# MB1297_MEMS.net
KiCad netlist of a schematic drawn in Altium Designer
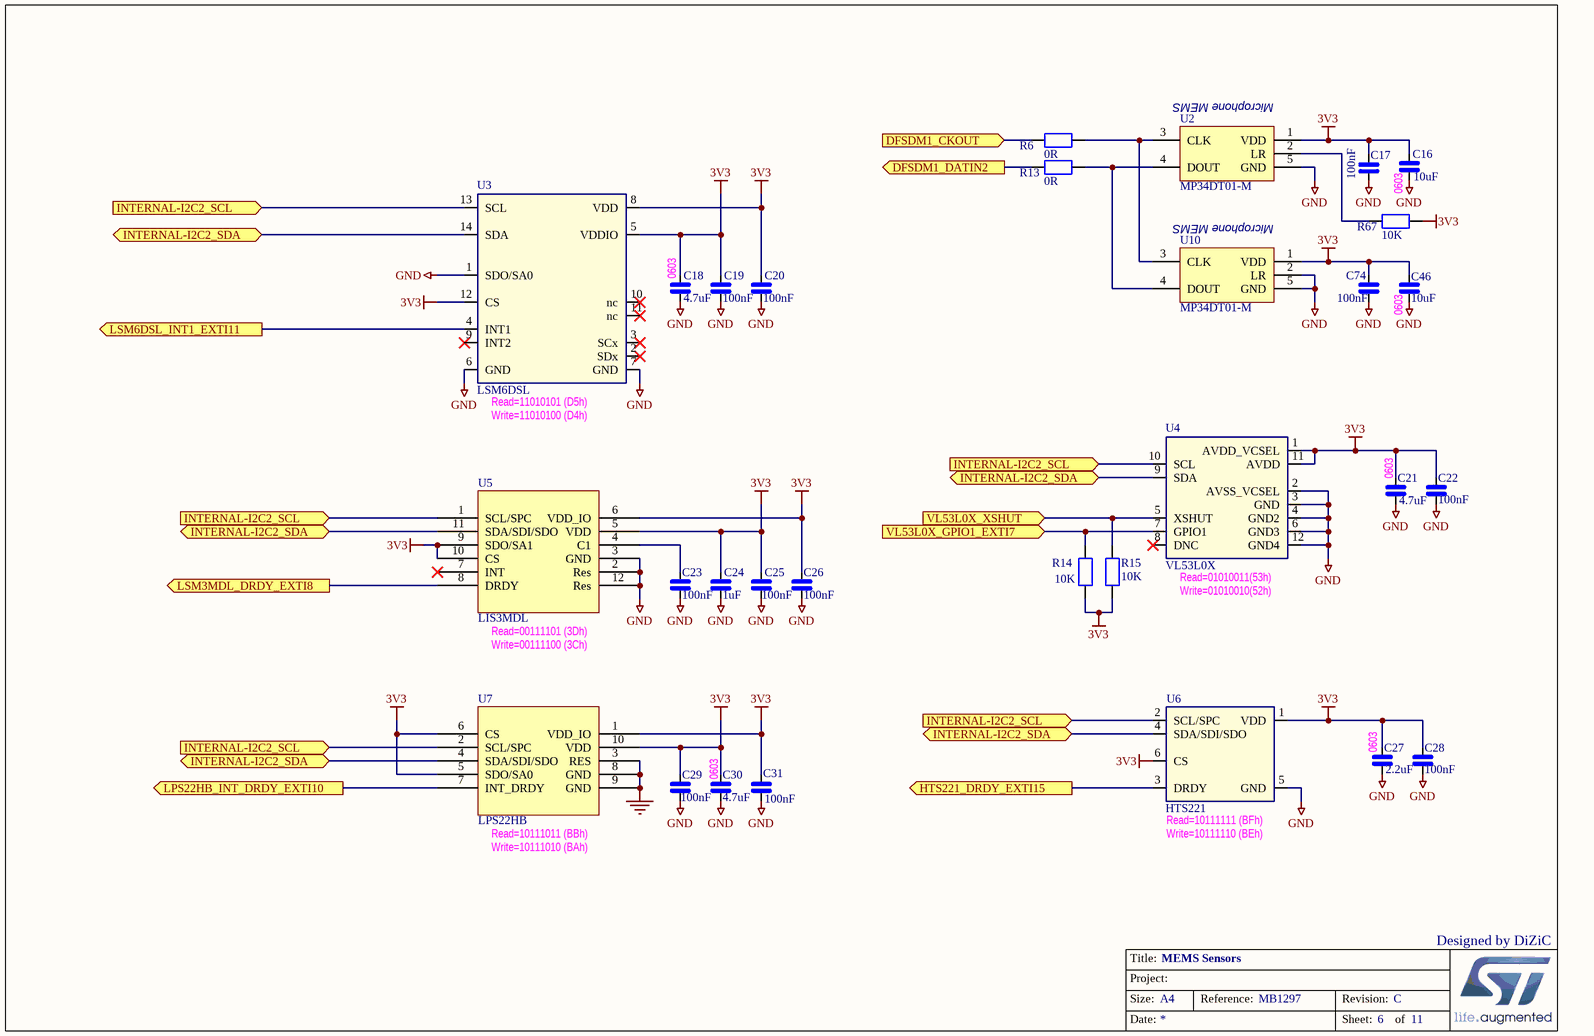
[diagram p0: MB1297_MEMS.SchDoc]

(export (version "E")
  (design (tool "Eeschema 10.0.6"))
  (components
    (comp (ref "C16")
      (value "10uF")
      (footprint "0603_CAP_NPOL")
      (description "Capacitor_not polarized")
      (libsource (lib "ST_Lib3D") (part "CAP_NPOL"))
    )
    (comp (ref "C17")
      (value "100nF")
      (footprint "0402_CAP_NPOL")
      (description "Capacitor_not polarized")
      (libsource (lib "ST_Lib3D") (part "CAP_NPOL"))
    )
    (comp (ref "C18")
      (value "4.7uF")
      (footprint "0603_CAP_NPOL")
      (description "Capacitor_not polarized")
      (libsource (lib "ST_Lib3D") (part "CAP_NPOL"))
    )
    (comp (ref "C19")
      (value "100nF")
      (footprint "0402_CAP_NPOL")
      (description "Capacitor_not polarized")
      (libsource (lib "ST_Lib3D") (part "CAP_NPOL"))
    )
    (comp (ref "C20")
      (value "100nF")
      (footprint "0402_CAP_NPOL")
      (description "Capacitor_not polarized")
      (libsource (lib "ST_Lib3D") (part "CAP_NPOL"))
    )
    (comp (ref "C21")
      (value "4.7uF")
      (footprint "0603_CAP_NPOL")
      (description "Capacitor_not polarized")
      (libsource (lib "ST_Lib3D") (part "CAP_NPOL"))
    )
    (comp (ref "C22")
      (value "100nF")
      (footprint "0402_CAP_NPOL")
      (description "Capacitor_not polarized")
      (libsource (lib "ST_Lib3D") (part "CAP_NPOL"))
    )
    (comp (ref "C23")
      (value "100nF")
      (footprint "0402_CAP_NPOL")
      (description "Capacitor_not polarized")
      (libsource (lib "ST_Lib3D") (part "CAP_NPOL"))
    )
    (comp (ref "C24")
      (value "1uF")
      (footprint "0402_CAP_NPOL")
      (description "Capacitor_not polarized")
      (libsource (lib "ST_Lib3D") (part "CAP_NPOL"))
    )
    (comp (ref "C25")
      (value "100nF")
      (footprint "0402_CAP_NPOL")
      (description "Capacitor_not polarized")
      (libsource (lib "ST_Lib3D") (part "CAP_NPOL"))
    )
    (comp (ref "C26")
      (value "100nF")
      (footprint "0402_CAP_NPOL")
      (description "Capacitor_not polarized")
      (libsource (lib "ST_Lib3D") (part "CAP_NPOL"))
    )
    (comp (ref "C27")
      (value "2.2uF")
      (footprint "0603_CAP_NPOL")
      (description "Capacitor_not polarized")
      (libsource (lib "ST_Lib3D") (part "CAP_NPOL"))
    )
    (comp (ref "C28")
      (value "100nF")
      (footprint "0402_CAP_NPOL")
      (description "Capacitor_not polarized")
      (libsource (lib "ST_Lib3D") (part "CAP_NPOL"))
    )
    (comp (ref "C29")
      (value "100nF")
      (footprint "0402_CAP_NPOL")
      (description "Capacitor_not polarized")
      (libsource (lib "ST_Lib3D") (part "CAP_NPOL"))
    )
    (comp (ref "C30")
      (value "4.7uF")
      (footprint "0603_CAP_NPOL")
      (description "Capacitor_not polarized")
      (libsource (lib "ST_Lib3D") (part "CAP_NPOL"))
    )
    (comp (ref "C31")
      (value "100nF")
      (footprint "0402_CAP_NPOL")
      (description "Capacitor_not polarized")
      (libsource (lib "ST_Lib3D") (part "CAP_NPOL"))
    )
    (comp (ref "C46")
      (value "10uF")
      (footprint "0603_CAP_NPOL")
      (description "Capacitor_not polarized")
      (libsource (lib "MB1297") (part "CAP_NPOL"))
    )
    (comp (ref "C74")
      (value "100nF")
      (footprint "0402_CAP_NPOL")
      (description "Capacitor_not polarized")
      (libsource (lib "MB1297") (part "CAP_NPOL"))
    )
    (comp (ref "R6")
      (value "0R")
      (footprint "0402_RES")
      (description "Resistor")
      (libsource (lib "ST_Lib3D") (part "RES"))
    )
    (comp (ref "R13")
      (value "0R")
      (footprint "0402_RES")
      (description "Resistor")
      (libsource (lib "ST_Lib3D") (part "RES"))
    )
    (comp (ref "R14")
      (value "10K")
      (footprint "0402_RES")
      (description "Resistor")
      (libsource (lib "ST_Lib3D") (part "RES"))
    )
    (comp (ref "R15")
      (value "10K")
      (footprint "0402_RES")
      (description "Resistor")
      (libsource (lib "ST_Lib3D") (part "RES"))
    )
    (comp (ref "R67")
      (value "10K")
      (footprint "0402_RES")
      (description "Resistor")
      (libsource (lib "ST_Lib3D") (part "RES"))
    )
    (comp (ref "U2")
      (value "MP34DT01-M")
      (footprint "HCLGA-4LD 3x4x1")
      (description "MEMS audio microphone")
      (libsource (lib "ST_Lib3D") (part "MP34DT01"))
    )
    (comp (ref "U3")
      (value "LSM6DSL")
      (footprint "LGA14L-2.5X3X0.86p0.5")
      (description "Accelero + Gyro MEMS (6 Axis)")
      (libsource (lib "ST_Lib3D") (part "LSM6DSL"))
    )
    (comp (ref "U4")
      (value "VL53L0X")
      (footprint "LGA12-optical")
      (description "Proximity sensor MEMS")
      (libsource (lib "ST_Lib3D") (part "VL53L0X"))
    )
    (comp (ref "U5")
      (value "LIS3MDL")
      (footprint "VFLGA12-2x2x1")
      (description "IC,Sensor")
      (fields (field (name "PROVIDER") "MMCC"))
      (libsource (lib "Semicon-ST") (part "LIS3MDL"))
    )
    (comp (ref "U6")
      (value "HTS221")
      (footprint "HLGA6L-2x2x0.9")
      (description "Humidity + Temp MEMS")
      (libsource (lib "ST_Lib3D") (part "HTS221"))
    )
    (comp (ref "U7")
      (value "LPS22HB")
      (footprint "HLGA10L-2X2X0.76")
      (description "IC,Sensor")
      (fields (field (name "PROVIDER") "MMCC"))
      (libsource (lib "ST_Lib3D") (part "LPS22HB"))
    )
    (comp (ref "U10")
      (value "MP34DT01-M")
      (footprint "HCLGA-4LD 3x4x1")
      (description "MEMS audio microphone")
      (libsource (lib "MB1297") (part "MP34DT01"))
    )
  )
  (nets
    (net (code "1") (name "/DFSDM1_CKOUT") (class "Default")
      (node (ref "R6") (pin "2") (pinfunction "2_2") (pintype "passive"))
    )
    (net (code "2") (name "/DFSDM1_DATIN2") (class "Default")
      (node (ref "R13") (pin "2") (pinfunction "2_2") (pintype "passive"))
    )
    (net (code "3") (name "/HTS221_DRDY_EXTI15") (class "Default")
      (node (ref "U6") (pin "3") (pinfunction "DRDY_3") (pintype "passive"))
    )
    (net (code "4") (name "/INTERNAL-I2C2_SCL") (class "Default")
      (node (ref "U3") (pin "13") (pinfunction "SCL_13") (pintype "passive"))
      (node (ref "U4") (pin "10") (pinfunction "SCL_10") (pintype "passive"))
      (node (ref "U5") (pin "1") (pinfunction "SCL/SPC_1") (pintype "passive"))
      (node (ref "U6") (pin "2") (pinfunction "SCL/SPC_2") (pintype "passive"))
      (node (ref "U7") (pin "2") (pinfunction "SCL/SPC_2") (pintype "passive"))
    )
    (net (code "5") (name "/INTERNAL-I2C2_SDA") (class "Default")
      (node (ref "U3") (pin "14") (pinfunction "SDA_14") (pintype "passive"))
      (node (ref "U4") (pin "9") (pinfunction "SDA_9") (pintype "passive"))
      (node (ref "U5") (pin "11") (pinfunction "SDA/SDI/SDO_11") (pintype "passive"))
      (node (ref "U6") (pin "4") (pinfunction "SDA/SDI/SDO_4") (pintype "passive"))
      (node (ref "U7") (pin "4") (pinfunction "SDA/SDI/SDO_4") (pintype "passive"))
    )
    (net (code "6") (name "/LPS22HB_INT_DRDY_EXTI10") (class "Default")
      (node (ref "U7") (pin "7") (pinfunction "INT_DRDY_7") (pintype "passive"))
    )
    (net (code "7") (name "/LSM3MDL_DRDY_EXTI8") (class "Default")
      (node (ref "U5") (pin "8") (pinfunction "DRDY_8") (pintype "passive"))
    )
    (net (code "8") (name "/LSM6DSL_INT1_EXTI11") (class "Default")
      (node (ref "U3") (pin "4") (pinfunction "INT1_4") (pintype "passive"))
    )
    (net (code "9") (name "/VL53L0X_GPIO1_EXTI7") (class "Default")
      (node (ref "R14") (pin "2") (pinfunction "2_2") (pintype "passive"))
      (node (ref "U4") (pin "7") (pinfunction "GPIO1_7") (pintype "passive"))
    )
    (net (code "10") (name "/VL53L0X_XSHUT") (class "Default")
      (node (ref "R15") (pin "2") (pinfunction "2_2") (pintype "passive"))
      (node (ref "U4") (pin "5") (pinfunction "XSHUT_5") (pintype "passive"))
    )
    (net (code "11") (name "3V3") (class "Default")
      (node (ref "C16") (pin "1") (pinfunction "1_1") (pintype "passive"))
      (node (ref "C17") (pin "2") (pinfunction "2_2") (pintype "passive"))
      (node (ref "C18") (pin "1") (pinfunction "1_1") (pintype "passive"))
      (node (ref "C19") (pin "1") (pinfunction "1_1") (pintype "passive"))
      (node (ref "C20") (pin "1") (pinfunction "1_1") (pintype "passive"))
      (node (ref "C21") (pin "1") (pinfunction "1_1") (pintype "passive"))
      (node (ref "C22") (pin "1") (pinfunction "1_1") (pintype "passive"))
      (node (ref "C24") (pin "1") (pinfunction "1_1") (pintype "passive"))
      (node (ref "C25") (pin "1") (pinfunction "1_1") (pintype "passive"))
      (node (ref "C26") (pin "1") (pinfunction "1_1") (pintype "passive"))
      (node (ref "C27") (pin "1") (pinfunction "1_1") (pintype "passive"))
      (node (ref "C28") (pin "1") (pinfunction "1_1") (pintype "passive"))
      (node (ref "C29") (pin "1") (pinfunction "1_1") (pintype "passive"))
      (node (ref "C30") (pin "1") (pinfunction "1_1") (pintype "passive"))
      (node (ref "C31") (pin "1") (pinfunction "1_1") (pintype "passive"))
      (node (ref "C46") (pin "1") (pinfunction "1_1") (pintype "passive"))
      (node (ref "C74") (pin "1") (pinfunction "1_1") (pintype "passive"))
      (node (ref "R14") (pin "1") (pinfunction "1_1") (pintype "passive"))
      (node (ref "R15") (pin "1") (pinfunction "1_1") (pintype "passive"))
      (node (ref "R67") (pin "1") (pinfunction "1_1") (pintype "passive"))
      (node (ref "U10") (pin "1") (pinfunction "VDD_1") (pintype "passive"))
      (node (ref "U2") (pin "1") (pinfunction "VDD_1") (pintype "passive"))
      (node (ref "U3") (pin "12") (pinfunction "CS_12") (pintype "passive"))
      (node (ref "U3") (pin "5") (pinfunction "VDDIO_5") (pintype "passive"))
      (node (ref "U3") (pin "8") (pinfunction "VDD_8") (pintype "passive"))
      (node (ref "U4") (pin "1") (pinfunction "AVDD_VCSEL_1") (pintype "passive"))
      (node (ref "U4") (pin "11") (pinfunction "AVDD_11") (pintype "passive"))
      (node (ref "U5") (pin "10") (pinfunction "CS_10") (pintype "passive"))
      (node (ref "U5") (pin "5") (pinfunction "VDD_5") (pintype "passive"))
      (node (ref "U5") (pin "6") (pinfunction "VDD_IO_6") (pintype "passive"))
      (node (ref "U5") (pin "9") (pinfunction "SDO/SA1_9") (pintype "passive"))
      (node (ref "U6") (pin "1") (pinfunction "VDD_1") (pintype "passive"))
      (node (ref "U6") (pin "6") (pinfunction "CS_6") (pintype "passive"))
      (node (ref "U7") (pin "1") (pinfunction "VDD_IO_1") (pintype "passive"))
      (node (ref "U7") (pin "10") (pinfunction "VDD_10") (pintype "passive"))
      (node (ref "U7") (pin "5") (pinfunction "SDO/SA0_5") (pintype "passive"))
      (node (ref "U7") (pin "6") (pinfunction "CS_6") (pintype "passive"))
    )
    (net (code "12") (name "GND") (class "Default")
      (node (ref "C16") (pin "2") (pinfunction "2_2") (pintype "passive"))
      (node (ref "C17") (pin "1") (pinfunction "1_1") (pintype "passive"))
      (node (ref "C18") (pin "2") (pinfunction "2_2") (pintype "passive"))
      (node (ref "C19") (pin "2") (pinfunction "2_2") (pintype "passive"))
      (node (ref "C20") (pin "2") (pinfunction "2_2") (pintype "passive"))
      (node (ref "C21") (pin "2") (pinfunction "2_2") (pintype "passive"))
      (node (ref "C22") (pin "2") (pinfunction "2_2") (pintype "passive"))
      (node (ref "C23") (pin "2") (pinfunction "2_2") (pintype "passive"))
      (node (ref "C24") (pin "2") (pinfunction "2_2") (pintype "passive"))
      (node (ref "C25") (pin "2") (pinfunction "2_2") (pintype "passive"))
      (node (ref "C26") (pin "2") (pinfunction "2_2") (pintype "passive"))
      (node (ref "C27") (pin "2") (pinfunction "2_2") (pintype "passive"))
      (node (ref "C28") (pin "2") (pinfunction "2_2") (pintype "passive"))
      (node (ref "C29") (pin "2") (pinfunction "2_2") (pintype "passive"))
      (node (ref "C30") (pin "2") (pinfunction "2_2") (pintype "passive"))
      (node (ref "C31") (pin "2") (pinfunction "2_2") (pintype "passive"))
      (node (ref "C46") (pin "2") (pinfunction "2_2") (pintype "passive"))
      (node (ref "C74") (pin "2") (pinfunction "2_2") (pintype "passive"))
      (node (ref "U10") (pin "2") (pinfunction "LR_2") (pintype "passive"))
      (node (ref "U10") (pin "5") (pinfunction "GND_5") (pintype "passive"))
      (node (ref "U2") (pin "5") (pinfunction "GND_5") (pintype "passive"))
      (node (ref "U3") (pin "1") (pinfunction "SDO/SA0_1") (pintype "passive"))
      (node (ref "U3") (pin "6") (pinfunction "GND_6") (pintype "passive"))
      (node (ref "U3") (pin "7") (pinfunction "GND_7") (pintype "passive"))
      (node (ref "U4") (pin "12") (pinfunction "GND4_12") (pintype "passive"))
      (node (ref "U4") (pin "2") (pinfunction "AVSS_VCSEL_2") (pintype "passive"))
      (node (ref "U4") (pin "3") (pinfunction "GND_3") (pintype "passive"))
      (node (ref "U4") (pin "4") (pinfunction "GND2_4") (pintype "passive"))
      (node (ref "U4") (pin "6") (pinfunction "GND3_6") (pintype "passive"))
      (node (ref "U5") (pin "12") (pinfunction "Res_12") (pintype "passive"))
      (node (ref "U5") (pin "2") (pinfunction "Res_2") (pintype "passive"))
      (node (ref "U5") (pin "3") (pinfunction "GND_3") (pintype "passive"))
      (node (ref "U6") (pin "5") (pinfunction "GND_5") (pintype "passive"))
      (node (ref "U7") (pin "3") (pinfunction "RES_3") (pintype "passive"))
      (node (ref "U7") (pin "8") (pinfunction "GND_8") (pintype "passive"))
      (node (ref "U7") (pin "9") (pinfunction "GND_9") (pintype "passive"))
    )
    (net (code "13") (name "Net-(U2-LR)") (class "Default")
      (node (ref "R67") (pin "2") (pinfunction "2_2") (pintype "passive"))
      (node (ref "U2") (pin "2") (pinfunction "LR_2") (pintype "passive"))
    )
    (net (code "14") (name "Net-(U5-C1)") (class "Default")
      (node (ref "C23") (pin "1") (pinfunction "1_1") (pintype "passive"))
      (node (ref "U5") (pin "4") (pinfunction "C1_4") (pintype "passive"))
    )
    (net (code "15") (name "Net-(U10-CLK)") (class "Default")
      (node (ref "R6") (pin "1") (pinfunction "1_1") (pintype "passive"))
      (node (ref "U10") (pin "3") (pinfunction "CLK_3") (pintype "passive"))
      (node (ref "U2") (pin "3") (pinfunction "CLK_3") (pintype "passive"))
    )
    (net (code "16") (name "Net-(U10-DOUT)") (class "Default")
      (node (ref "R13") (pin "1") (pinfunction "1_1") (pintype "passive"))
      (node (ref "U10") (pin "4") (pinfunction "DOUT_4") (pintype "passive"))
      (node (ref "U2") (pin "4") (pinfunction "DOUT_4") (pintype "passive"))
    )
    (net (code "17") (name "unconnected-(U3-INT2-Pad9)") (class "Default")
      (node (ref "U3") (pin "9") (pinfunction "INT2_9") (pintype "passive+no_connect"))
    )
    (net (code "18") (name "unconnected-(U3-SCx-Pad3)") (class "Default")
      (node (ref "U3") (pin "3") (pinfunction "SCx_3") (pintype "passive+no_connect"))
    )
    (net (code "19") (name "unconnected-(U3-SDx-Pad2)") (class "Default")
      (node (ref "U3") (pin "2") (pinfunction "SDx_2") (pintype "passive+no_connect"))
    )
    (net (code "20") (name "unconnected-(U3-nc-Pad10)") (class "Default")
      (node (ref "U3") (pin "10") (pinfunction "nc_10") (pintype "passive+no_connect"))
    )
    (net (code "21") (name "unconnected-(U3-nc-Pad11)") (class "Default")
      (node (ref "U3") (pin "11") (pinfunction "nc_11") (pintype "passive+no_connect"))
    )
    (net (code "22") (name "unconnected-(U4-DNC-Pad8)") (class "Default")
      (node (ref "U4") (pin "8") (pinfunction "DNC_8") (pintype "passive+no_connect"))
    )
    (net (code "23") (name "unconnected-(U5-INT-Pad7)") (class "Default")
      (node (ref "U5") (pin "7") (pinfunction "INT_7") (pintype "passive+no_connect"))
    )
  )
)
